# FDTI_USB_Card.net
KiCad netlist of a schematic drawn in Altium Designer
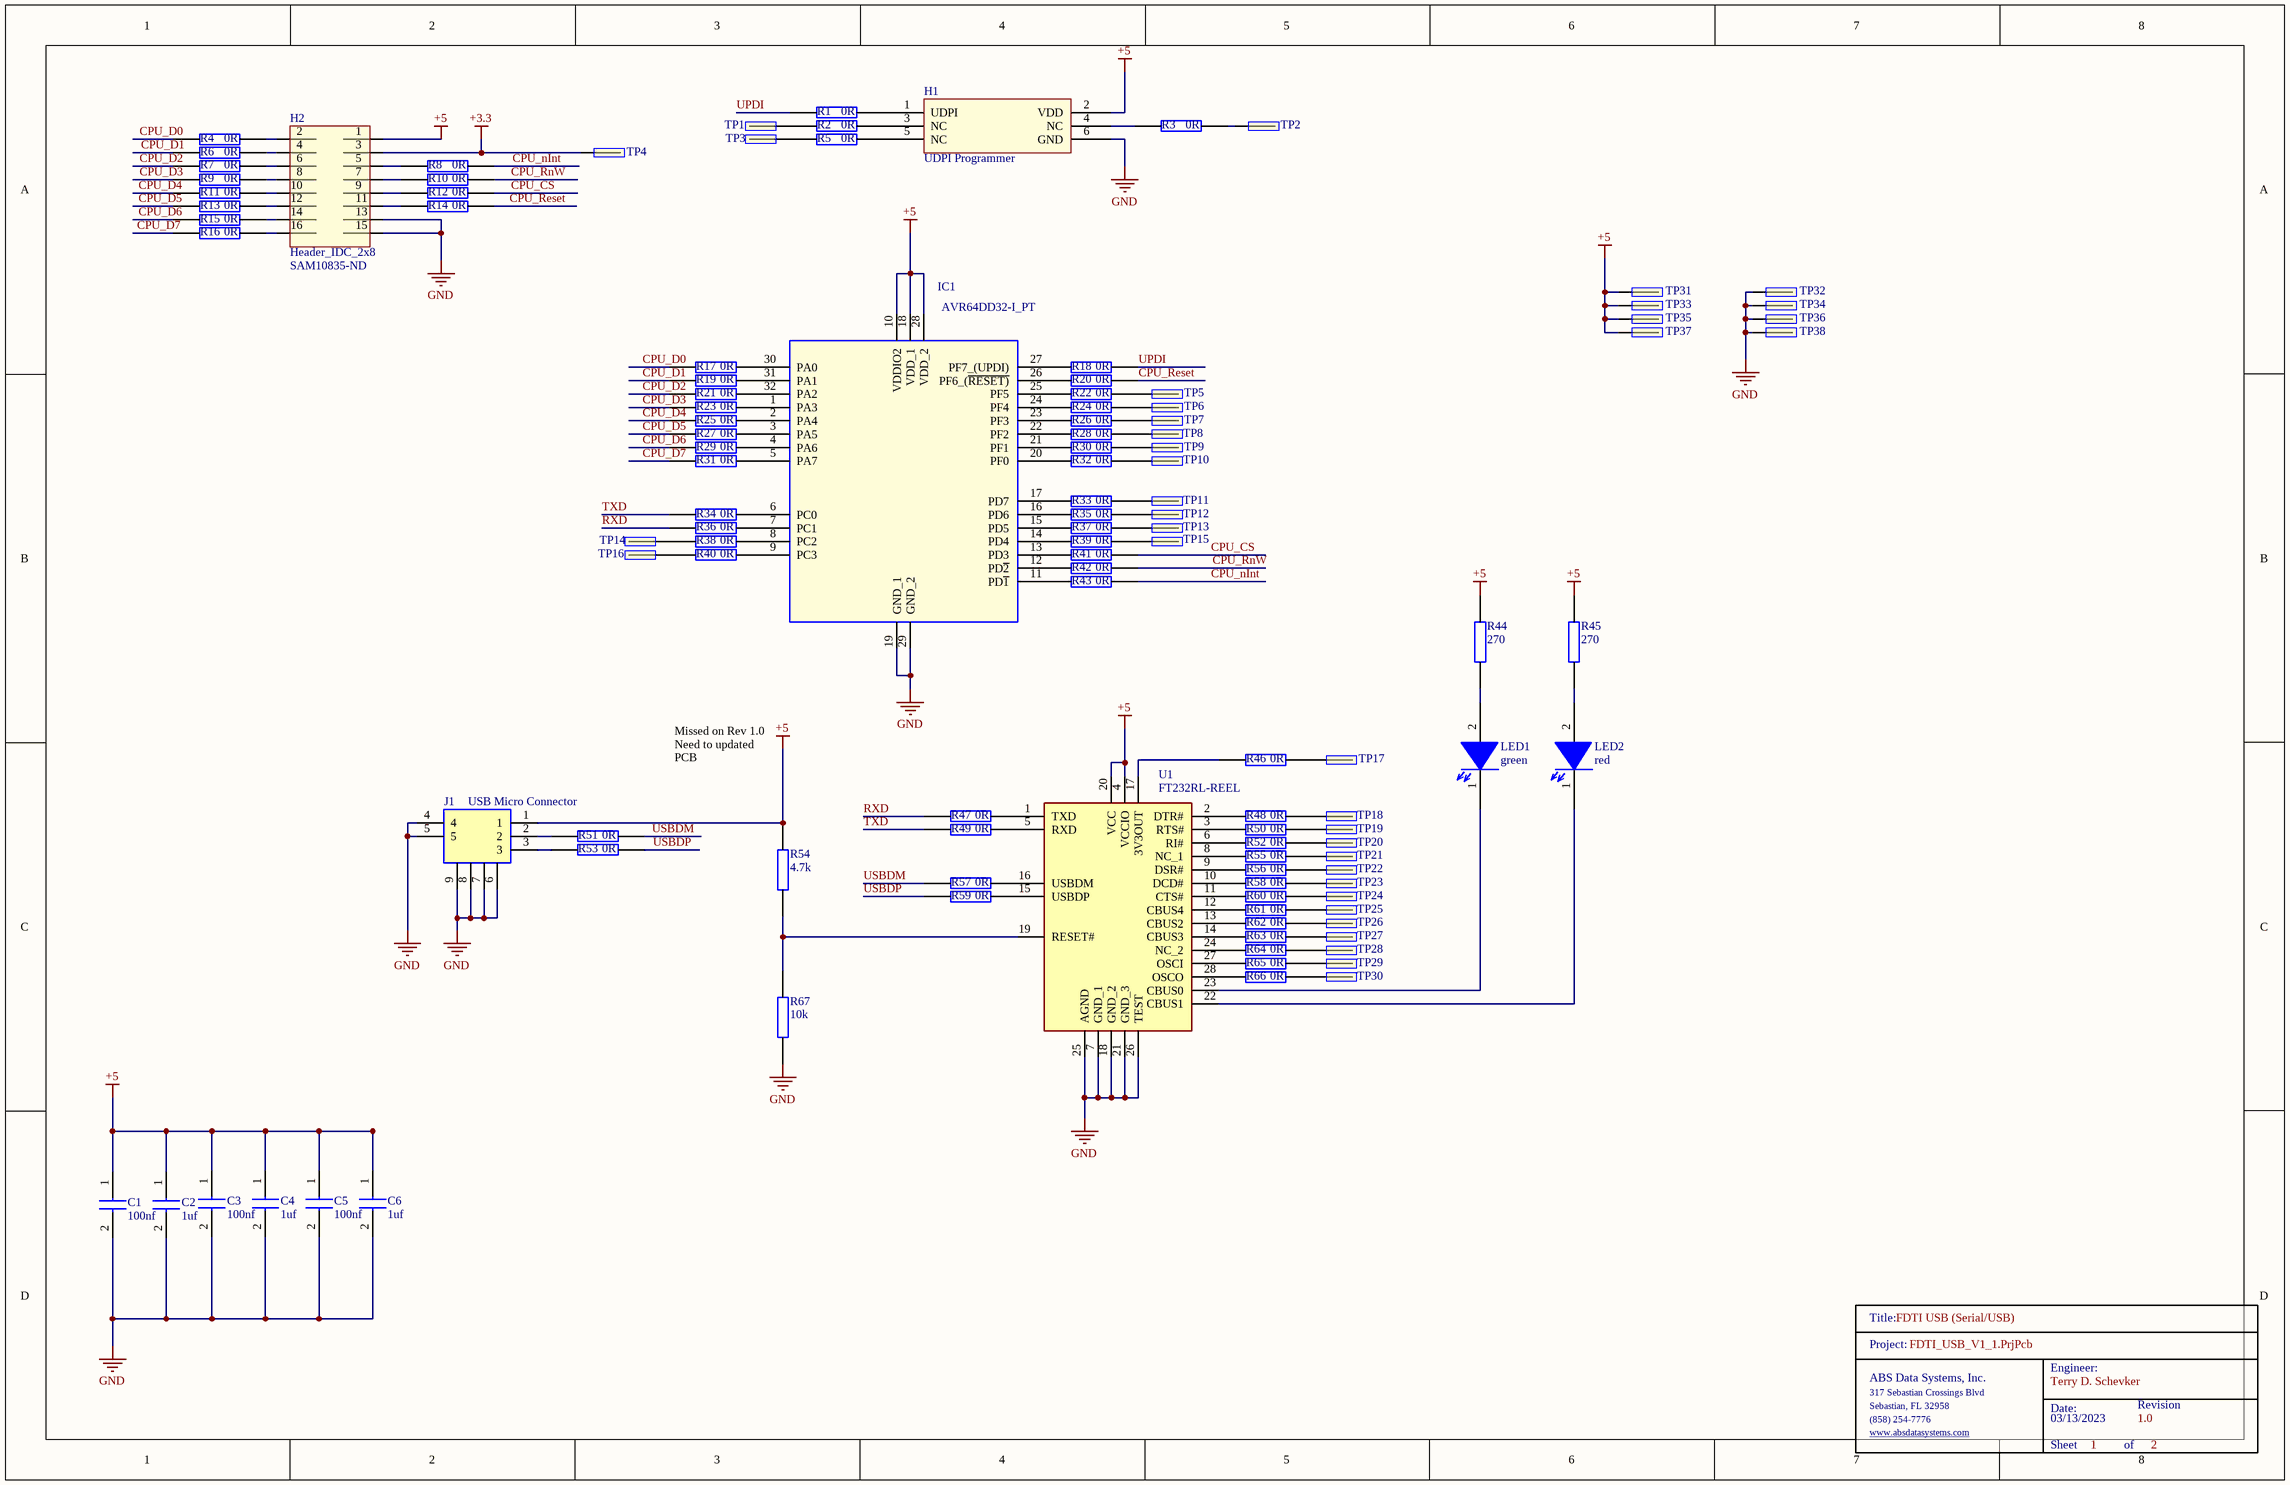
[diagram p0: FDTI_USB_Card.SchDoc]

(export (version "E")
  (design (tool "Eeschema 10.0.6"))
  (components
    (comp (ref "C1")
      (value "100nf")
      (footprint "0603")
      (description "Samsung Electro-Mechanics 0603 100nf")
      (libsource (lib "Capacitors") (part "CL10B104JB8NNNC"))
    )
    (comp (ref "C2")
      (value "1uf")
      (footprint "0603")
      (description "Samsung Electro-Mechanics 0603 1uf")
      (libsource (lib "Capacitors") (part "CL10B105KA8NNNL"))
    )
    (comp (ref "C3")
      (value "100nf")
      (footprint "0603")
      (description "Samsung Electro-Mechanics 0603 100nf")
      (libsource (lib "Capacitors") (part "CL10B104JB8NNNC"))
    )
    (comp (ref "C4")
      (value "1uf")
      (footprint "0603")
      (description "Samsung Electro-Mechanics 0603 1uf")
      (libsource (lib "Capacitors") (part "CL10B105KA8NNNL"))
    )
    (comp (ref "C5")
      (value "100nf")
      (footprint "0603")
      (description "Samsung Electro-Mechanics 0603 100nf")
      (libsource (lib "Capacitors") (part "CL10B104JB8NNNC"))
    )
    (comp (ref "C6")
      (value "1uf")
      (footprint "0603")
      (description "Samsung Electro-Mechanics 0603 1uf")
      (libsource (lib "Capacitors") (part "CL10B105KA8NNNL"))
    )
    (comp (ref "H1")
      (value "UDPI Programmer")
      (footprint "HDR2X3")
      (description "6 Pin 2X3 Through Hole Header")
      (libsource (lib "Misc") (part "UDPI Programmer"))
    )
    (comp (ref "H2")
      (value "Header_IDC_2x8")
      (footprint "HEADER16")
      (description "16 Pin 2x8 Through Hold IDC Connector")
      (fields
        (field (name "MANUFACTURER") "Samtec")
        (field (name "MANUFACTURER PART NUMBER") "TST-108-01-G-D")
        (field (name "SUPPLIER PART NUMBER 1") "SAM10835-ND")
      )
      (libsource (lib "Misc") (part "Header_IDC_2x8"))
    )
    (comp (ref "IC1")
      (value "AVR64DD32-I_PT")
      (footprint "QFP80P900X900X120-32N")
      (description "Integrated Circuit")
      (fields (field (name "MANUFACTURER_PART_NUMBER") "AVR64DD32-I/PT ¦ MULTI-VOLTAGE I/O"))
      (libsource (lib "CPU_Memory") (part "AVR64DD32-I_PT"))
    )
    (comp (ref "J1")
      (value "USB Micro Connector")
      (footprint "Connectors:1734035-2USB")
      (description "USB Micro Connector SMD")
      (fields
        (field (name "MOUSER2 PART NUMBER") "571-1734035-4")
        (field (name "MANUFACTURER_PART_NUMBER") "1734035-4")
      )
      (libsource (lib "Connectors") (part "1734035-4"))
    )
    (comp (ref "LED1")
      (value "green")
      (footprint "0603_Diode")
      (description "Wurth Elektronik 0603 green")
      (fields
        (field (name "MANUFACTURER") "Wurth Electronics")
        (field (name "MANUFACTURER PART NUMBER") "150060GS75000")
      )
      (libsource (lib "Misc") (part "150060GS75000"))
    )
    (comp (ref "LED2")
      (value "red")
      (footprint "0603_Diode")
      (description "Wurth Elektronik 0603 red")
      (fields
        (field (name "MANUFACTURER") "Wurth Electronics")
        (field (name "MANUFACTURER PART NUMBER") "150060GS75000")
      )
      (libsource (lib "Misc") (part "150060RS75000"))
    )
    (comp (ref "R1")
      (value "0R")
      (footprint "0603")
      (description "YAGEO 0603 0 ohm")
      (fields
        (field (name "MOUSER PART NUMBER") "603-RC0603JR-070RL")
        (field (name "MANUFACTURER_PART_NUMBER") "RC0603JR-070RL")
      )
      (libsource (lib "Resistors") (part "RC0603JR-070RL"))
    )
    (comp (ref "R2")
      (value "0R")
      (footprint "0603")
      (description "YAGEO 0603 0 ohm")
      (fields
        (field (name "MOUSER PART NUMBER") "603-RC0603JR-070RL")
        (field (name "MANUFACTURER_PART_NUMBER") "RC0603JR-070RL")
      )
      (libsource (lib "Resistors") (part "RC0603JR-070RL"))
    )
    (comp (ref "R3")
      (value "0R")
      (footprint "0603")
      (description "YAGEO 0603 0 ohm")
      (fields
        (field (name "MOUSER PART NUMBER") "603-RC0603JR-070RL")
        (field (name "MANUFACTURER_PART_NUMBER") "RC0603JR-070RL")
      )
      (libsource (lib "Resistors") (part "RC0603JR-070RL"))
    )
    (comp (ref "R4")
      (value "0R")
      (footprint "0603")
      (description "YAGEO 0603 0 ohm")
      (fields
        (field (name "MOUSER PART NUMBER") "603-RC0603JR-070RL")
        (field (name "MANUFACTURER_PART_NUMBER") "RC0603JR-070RL")
      )
      (libsource (lib "Resistors") (part "RC0603JR-070RL"))
    )
    (comp (ref "R5")
      (value "0R")
      (footprint "0603")
      (description "YAGEO 0603 0 ohm")
      (fields
        (field (name "MOUSER PART NUMBER") "603-RC0603JR-070RL")
        (field (name "MANUFACTURER_PART_NUMBER") "RC0603JR-070RL")
      )
      (libsource (lib "Resistors") (part "RC0603JR-070RL"))
    )
    (comp (ref "R6")
      (value "0R")
      (footprint "0603")
      (description "YAGEO 0603 0 ohm")
      (fields
        (field (name "MOUSER PART NUMBER") "603-RC0603JR-070RL")
        (field (name "MANUFACTURER_PART_NUMBER") "RC0603JR-070RL")
      )
      (libsource (lib "Resistors") (part "RC0603JR-070RL"))
    )
    (comp (ref "R7")
      (value "0R")
      (footprint "0603")
      (description "YAGEO 0603 0 ohm")
      (fields
        (field (name "MOUSER PART NUMBER") "603-RC0603JR-070RL")
        (field (name "MANUFACTURER_PART_NUMBER") "RC0603JR-070RL")
      )
      (libsource (lib "Resistors") (part "RC0603JR-070RL"))
    )
    (comp (ref "R8")
      (value "0R")
      (footprint "0603")
      (description "YAGEO 0603 0 ohm")
      (fields
        (field (name "MOUSER PART NUMBER") "603-RC0603JR-070RL")
        (field (name "MANUFACTURER_PART_NUMBER") "RC0603JR-070RL")
      )
      (libsource (lib "Resistors") (part "RC0603JR-070RL"))
    )
    (comp (ref "R9")
      (value "0R")
      (footprint "0603")
      (description "YAGEO 0603 0 ohm")
      (fields
        (field (name "MOUSER PART NUMBER") "603-RC0603JR-070RL")
        (field (name "MANUFACTURER_PART_NUMBER") "RC0603JR-070RL")
      )
      (libsource (lib "Resistors") (part "RC0603JR-070RL"))
    )
    (comp (ref "R10")
      (value "0R")
      (footprint "0603")
      (description "YAGEO 0603 0 ohm")
      (fields
        (field (name "MOUSER PART NUMBER") "603-RC0603JR-070RL")
        (field (name "MANUFACTURER_PART_NUMBER") "RC0603JR-070RL")
      )
      (libsource (lib "Resistors") (part "RC0603JR-070RL"))
    )
    (comp (ref "R11")
      (value "0R")
      (footprint "0603")
      (description "YAGEO 0603 0 ohm")
      (fields
        (field (name "MOUSER PART NUMBER") "603-RC0603JR-070RL")
        (field (name "MANUFACTURER_PART_NUMBER") "RC0603JR-070RL")
      )
      (libsource (lib "Resistors") (part "RC0603JR-070RL"))
    )
    (comp (ref "R12")
      (value "0R")
      (footprint "0603")
      (description "YAGEO 0603 0 ohm")
      (fields
        (field (name "MOUSER PART NUMBER") "603-RC0603JR-070RL")
        (field (name "MANUFACTURER_PART_NUMBER") "RC0603JR-070RL")
      )
      (libsource (lib "Resistors") (part "RC0603JR-070RL"))
    )
    (comp (ref "R13")
      (value "0R")
      (footprint "0603")
      (description "YAGEO 0603 0 ohm")
      (fields
        (field (name "MOUSER PART NUMBER") "603-RC0603JR-070RL")
        (field (name "MANUFACTURER_PART_NUMBER") "RC0603JR-070RL")
      )
      (libsource (lib "Resistors") (part "RC0603JR-070RL"))
    )
    (comp (ref "R14")
      (value "0R")
      (footprint "0603")
      (description "YAGEO 0603 0 ohm")
      (fields
        (field (name "MOUSER PART NUMBER") "603-RC0603JR-070RL")
        (field (name "MANUFACTURER_PART_NUMBER") "RC0603JR-070RL")
      )
      (libsource (lib "Resistors") (part "RC0603JR-070RL"))
    )
    (comp (ref "R15")
      (value "0R")
      (footprint "0603")
      (description "YAGEO 0603 0 ohm")
      (fields
        (field (name "MOUSER PART NUMBER") "603-RC0603JR-070RL")
        (field (name "MANUFACTURER_PART_NUMBER") "RC0603JR-070RL")
      )
      (libsource (lib "Resistors") (part "RC0603JR-070RL"))
    )
    (comp (ref "R16")
      (value "0R")
      (footprint "0603")
      (description "YAGEO 0603 0 ohm")
      (fields
        (field (name "MOUSER PART NUMBER") "603-RC0603JR-070RL")
        (field (name "MANUFACTURER_PART_NUMBER") "RC0603JR-070RL")
      )
      (libsource (lib "Resistors") (part "RC0603JR-070RL"))
    )
    (comp (ref "R17")
      (value "0R")
      (footprint "0603")
      (description "YAGEO 0603 0 ohm")
      (fields
        (field (name "MOUSER PART NUMBER") "603-RC0603JR-070RL")
        (field (name "MANUFACTURER_PART_NUMBER") "RC0603JR-070RL")
      )
      (libsource (lib "Resistors") (part "RC0603JR-070RL"))
    )
    (comp (ref "R18")
      (value "0R")
      (footprint "0603")
      (description "YAGEO 0603 0 ohm")
      (fields
        (field (name "MOUSER PART NUMBER") "603-RC0603JR-070RL")
        (field (name "MANUFACTURER_PART_NUMBER") "RC0603JR-070RL")
      )
      (libsource (lib "Resistors") (part "RC0603JR-070RL"))
    )
    (comp (ref "R19")
      (value "0R")
      (footprint "0603")
      (description "YAGEO 0603 0 ohm")
      (fields
        (field (name "MOUSER PART NUMBER") "603-RC0603JR-070RL")
        (field (name "MANUFACTURER_PART_NUMBER") "RC0603JR-070RL")
      )
      (libsource (lib "Resistors") (part "RC0603JR-070RL"))
    )
    (comp (ref "R20")
      (value "0R")
      (footprint "0603")
      (description "YAGEO 0603 0 ohm")
      (fields
        (field (name "MOUSER PART NUMBER") "603-RC0603JR-070RL")
        (field (name "MANUFACTURER_PART_NUMBER") "RC0603JR-070RL")
      )
      (libsource (lib "Resistors") (part "RC0603JR-070RL"))
    )
    (comp (ref "R21")
      (value "0R")
      (footprint "0603")
      (description "YAGEO 0603 0 ohm")
      (fields
        (field (name "MOUSER PART NUMBER") "603-RC0603JR-070RL")
        (field (name "MANUFACTURER_PART_NUMBER") "RC0603JR-070RL")
      )
      (libsource (lib "Resistors") (part "RC0603JR-070RL"))
    )
    (comp (ref "R22")
      (value "0R")
      (footprint "0603")
      (description "YAGEO 0603 0 ohm")
      (fields
        (field (name "MOUSER PART NUMBER") "603-RC0603JR-070RL")
        (field (name "MANUFACTURER_PART_NUMBER") "RC0603JR-070RL")
      )
      (libsource (lib "Resistors") (part "RC0603JR-070RL"))
    )
    (comp (ref "R23")
      (value "0R")
      (footprint "0603")
      (description "YAGEO 0603 0 ohm")
      (fields
        (field (name "MOUSER PART NUMBER") "603-RC0603JR-070RL")
        (field (name "MANUFACTURER_PART_NUMBER") "RC0603JR-070RL")
      )
      (libsource (lib "Resistors") (part "RC0603JR-070RL"))
    )
    (comp (ref "R24")
      (value "0R")
      (footprint "0603")
      (description "YAGEO 0603 0 ohm")
      (fields
        (field (name "MOUSER PART NUMBER") "603-RC0603JR-070RL")
        (field (name "MANUFACTURER_PART_NUMBER") "RC0603JR-070RL")
      )
      (libsource (lib "Resistors") (part "RC0603JR-070RL"))
    )
    (comp (ref "R25")
      (value "0R")
      (footprint "0603")
      (description "YAGEO 0603 0 ohm")
      (fields
        (field (name "MOUSER PART NUMBER") "603-RC0603JR-070RL")
        (field (name "MANUFACTURER_PART_NUMBER") "RC0603JR-070RL")
      )
      (libsource (lib "Resistors") (part "RC0603JR-070RL"))
    )
    (comp (ref "R26")
      (value "0R")
      (footprint "0603")
      (description "YAGEO 0603 0 ohm")
      (fields
        (field (name "MOUSER PART NUMBER") "603-RC0603JR-070RL")
        (field (name "MANUFACTURER_PART_NUMBER") "RC0603JR-070RL")
      )
      (libsource (lib "Resistors") (part "RC0603JR-070RL"))
    )
    (comp (ref "R27")
      (value "0R")
      (footprint "0603")
      (description "YAGEO 0603 0 ohm")
      (fields
        (field (name "MOUSER PART NUMBER") "603-RC0603JR-070RL")
        (field (name "MANUFACTURER_PART_NUMBER") "RC0603JR-070RL")
      )
      (libsource (lib "Resistors") (part "RC0603JR-070RL"))
    )
    (comp (ref "R28")
      (value "0R")
      (footprint "0603")
      (description "YAGEO 0603 0 ohm")
      (fields
        (field (name "MOUSER PART NUMBER") "603-RC0603JR-070RL")
        (field (name "MANUFACTURER_PART_NUMBER") "RC0603JR-070RL")
      )
      (libsource (lib "Resistors") (part "RC0603JR-070RL"))
    )
    (comp (ref "R29")
      (value "0R")
      (footprint "0603")
      (description "YAGEO 0603 0 ohm")
      (fields
        (field (name "MOUSER PART NUMBER") "603-RC0603JR-070RL")
        (field (name "MANUFACTURER_PART_NUMBER") "RC0603JR-070RL")
      )
      (libsource (lib "Resistors") (part "RC0603JR-070RL"))
    )
    (comp (ref "R30")
      (value "0R")
      (footprint "0603")
      (description "YAGEO 0603 0 ohm")
      (fields
        (field (name "MOUSER PART NUMBER") "603-RC0603JR-070RL")
        (field (name "MANUFACTURER_PART_NUMBER") "RC0603JR-070RL")
      )
      (libsource (lib "Resistors") (part "RC0603JR-070RL"))
    )
    (comp (ref "R31")
      (value "0R")
      (footprint "0603")
      (description "YAGEO 0603 0 ohm")
      (fields
        (field (name "MOUSER PART NUMBER") "603-RC0603JR-070RL")
        (field (name "MANUFACTURER_PART_NUMBER") "RC0603JR-070RL")
      )
      (libsource (lib "Resistors") (part "RC0603JR-070RL"))
    )
    (comp (ref "R32")
      (value "0R")
      (footprint "0603")
      (description "YAGEO 0603 0 ohm")
      (fields
        (field (name "MOUSER PART NUMBER") "603-RC0603JR-070RL")
        (field (name "MANUFACTURER_PART_NUMBER") "RC0603JR-070RL")
      )
      (libsource (lib "Resistors") (part "RC0603JR-070RL"))
    )
    (comp (ref "R33")
      (value "0R")
      (footprint "0603")
      (description "YAGEO 0603 0 ohm")
      (fields
        (field (name "MOUSER PART NUMBER") "603-RC0603JR-070RL")
        (field (name "MANUFACTURER_PART_NUMBER") "RC0603JR-070RL")
      )
      (libsource (lib "Resistors") (part "RC0603JR-070RL"))
    )
    (comp (ref "R34")
      (value "0R")
      (footprint "0603")
      (description "YAGEO 0603 0 ohm")
      (fields
        (field (name "MOUSER PART NUMBER") "603-RC0603JR-070RL")
        (field (name "MANUFACTURER_PART_NUMBER") "RC0603JR-070RL")
      )
      (libsource (lib "Resistors") (part "RC0603JR-070RL"))
    )
    (comp (ref "R35")
      (value "0R")
      (footprint "0603")
      (description "YAGEO 0603 0 ohm")
      (fields
        (field (name "MOUSER PART NUMBER") "603-RC0603JR-070RL")
        (field (name "MANUFACTURER_PART_NUMBER") "RC0603JR-070RL")
      )
      (libsource (lib "Resistors") (part "RC0603JR-070RL"))
    )
    (comp (ref "R36")
      (value "0R")
      (footprint "0603")
      (description "YAGEO 0603 0 ohm")
      (fields
        (field (name "MOUSER PART NUMBER") "603-RC0603JR-070RL")
        (field (name "MANUFACTURER_PART_NUMBER") "RC0603JR-070RL")
      )
      (libsource (lib "Resistors") (part "RC0603JR-070RL"))
    )
    (comp (ref "R37")
      (value "0R")
      (footprint "0603")
      (description "YAGEO 0603 0 ohm")
      (fields
        (field (name "MOUSER PART NUMBER") "603-RC0603JR-070RL")
        (field (name "MANUFACTURER_PART_NUMBER") "RC0603JR-070RL")
      )
      (libsource (lib "Resistors") (part "RC0603JR-070RL"))
    )
    (comp (ref "R38")
      (value "0R")
      (footprint "0603")
      (description "YAGEO 0603 0 ohm")
      (fields
        (field (name "MOUSER PART NUMBER") "603-RC0603JR-070RL")
        (field (name "MANUFACTURER_PART_NUMBER") "RC0603JR-070RL")
      )
      (libsource (lib "Resistors") (part "RC0603JR-070RL"))
    )
    (comp (ref "R39")
      (value "0R")
      (footprint "0603")
      (description "YAGEO 0603 0 ohm")
      (fields
        (field (name "MOUSER PART NUMBER") "603-RC0603JR-070RL")
        (field (name "MANUFACTURER_PART_NUMBER") "RC0603JR-070RL")
      )
      (libsource (lib "Resistors") (part "RC0603JR-070RL"))
    )
    (comp (ref "R40")
      (value "0R")
      (footprint "0603")
      (description "YAGEO 0603 0 ohm")
      (fields
        (field (name "MOUSER PART NUMBER") "603-RC0603JR-070RL")
        (field (name "MANUFACTURER_PART_NUMBER") "RC0603JR-070RL")
      )
      (libsource (lib "Resistors") (part "RC0603JR-070RL"))
    )
    (comp (ref "R41")
      (value "0R")
      (footprint "0603")
      (description "YAGEO 0603 0 ohm")
      (fields
        (field (name "MOUSER PART NUMBER") "603-RC0603JR-070RL")
        (field (name "MANUFACTURER_PART_NUMBER") "RC0603JR-070RL")
      )
      (libsource (lib "Resistors") (part "RC0603JR-070RL"))
    )
    (comp (ref "R42")
      (value "0R")
      (footprint "0603")
      (description "YAGEO 0603 0 ohm")
      (fields
        (field (name "MOUSER PART NUMBER") "603-RC0603JR-070RL")
        (field (name "MANUFACTURER_PART_NUMBER") "RC0603JR-070RL")
      )
      (libsource (lib "Resistors") (part "RC0603JR-070RL"))
    )
    (comp (ref "R43")
      (value "0R")
      (footprint "0603")
      (description "YAGEO 0603 0 ohm")
      (fields
        (field (name "MOUSER PART NUMBER") "603-RC0603JR-070RL")
        (field (name "MANUFACTURER_PART_NUMBER") "RC0603JR-070RL")
      )
      (libsource (lib "Resistors") (part "RC0603JR-070RL"))
    )
    (comp (ref "R44")
      (value "270")
      (footprint "0603")
      (description "YAGEO 0603 270 ohm")
      (fields
        (field (name "MOUSER PART NUMBER") "603-RC0603JR-070RL")
        (field (name "MANUFACTURER_PART_NUMBER") "RC0603JR-070RL")
      )
      (libsource (lib "Resistors") (part "RC0603JR-07270RL"))
    )
    (comp (ref "R45")
      (value "270")
      (footprint "0603")
      (description "YAGEO 0603 270 ohm")
      (fields
        (field (name "MOUSER PART NUMBER") "603-RC0603JR-070RL")
        (field (name "MANUFACTURER_PART_NUMBER") "RC0603JR-070RL")
      )
      (libsource (lib "Resistors") (part "RC0603JR-07270RL"))
    )
    (comp (ref "R46")
      (value "0R")
      (footprint "0603")
      (description "YAGEO 0603 0 ohm")
      (fields
        (field (name "MOUSER PART NUMBER") "603-RC0603JR-070RL")
        (field (name "MANUFACTURER_PART_NUMBER") "RC0603JR-070RL")
      )
      (libsource (lib "Resistors") (part "RC0603JR-070RL"))
    )
    (comp (ref "R47")
      (value "0R")
      (footprint "0603")
      (description "YAGEO 0603 0 ohm")
      (fields
        (field (name "MOUSER PART NUMBER") "603-RC0603JR-070RL")
        (field (name "MANUFACTURER_PART_NUMBER") "RC0603JR-070RL")
      )
      (libsource (lib "Resistors") (part "RC0603JR-070RL"))
    )
    (comp (ref "R48")
      (value "0R")
      (footprint "0603")
      (description "YAGEO 0603 0 ohm")
      (fields
        (field (name "MOUSER PART NUMBER") "603-RC0603JR-070RL")
        (field (name "MANUFACTURER_PART_NUMBER") "RC0603JR-070RL")
      )
      (libsource (lib "Resistors") (part "RC0603JR-070RL"))
    )
    (comp (ref "R49")
      (value "0R")
      (footprint "0603")
      (description "YAGEO 0603 0 ohm")
      (fields
        (field (name "MOUSER PART NUMBER") "603-RC0603JR-070RL")
        (field (name "MANUFACTURER_PART_NUMBER") "RC0603JR-070RL")
      )
      (libsource (lib "Resistors") (part "RC0603JR-070RL"))
    )
    (comp (ref "R50")
      (value "0R")
      (footprint "0603")
      (description "YAGEO 0603 0 ohm")
      (fields
        (field (name "MOUSER PART NUMBER") "603-RC0603JR-070RL")
        (field (name "MANUFACTURER_PART_NUMBER") "RC0603JR-070RL")
      )
      (libsource (lib "Resistors") (part "RC0603JR-070RL"))
    )
    (comp (ref "R51")
      (value "0R")
      (footprint "0603")
      (description "YAGEO 0603 0 ohm")
      (fields
        (field (name "MOUSER PART NUMBER") "603-RC0603JR-070RL")
        (field (name "MANUFACTURER_PART_NUMBER") "RC0603JR-070RL")
      )
      (libsource (lib "Resistors") (part "RC0603JR-070RL"))
    )
    (comp (ref "R52")
      (value "0R")
      (footprint "0603")
      (description "YAGEO 0603 0 ohm")
      (fields
        (field (name "MOUSER PART NUMBER") "603-RC0603JR-070RL")
        (field (name "MANUFACTURER_PART_NUMBER") "RC0603JR-070RL")
      )
      (libsource (lib "Resistors") (part "RC0603JR-070RL"))
    )
    (comp (ref "R53")
      (value "0R")
      (footprint "0603")
      (description "YAGEO 0603 0 ohm")
      (fields
        (field (name "MOUSER PART NUMBER") "603-RC0603JR-070RL")
        (field (name "MANUFACTURER_PART_NUMBER") "RC0603JR-070RL")
      )
      (libsource (lib "Resistors") (part "RC0603JR-070RL"))
    )
    (comp (ref "R54")
      (value "4.7k")
      (footprint "0603")
      (description "YAGEO 0603 4.7k")
      (fields
        (field (name "MOUSER PART NUMBER") "603-RC0603JR-070RL")
        (field (name "MANUFACTURER_PART_NUMBER") "RC0603JR-070RL")
      )
      (libsource (lib "Resistors") (part "RC0603FR-104K7L"))
    )
    (comp (ref "R55")
      (value "0R")
      (footprint "0603")
      (description "YAGEO 0603 0 ohm")
      (fields
        (field (name "MOUSER PART NUMBER") "603-RC0603JR-070RL")
        (field (name "MANUFACTURER_PART_NUMBER") "RC0603JR-070RL")
      )
      (libsource (lib "Resistors") (part "RC0603JR-070RL"))
    )
    (comp (ref "R56")
      (value "0R")
      (footprint "0603")
      (description "YAGEO 0603 0 ohm")
      (fields
        (field (name "MOUSER PART NUMBER") "603-RC0603JR-070RL")
        (field (name "MANUFACTURER_PART_NUMBER") "RC0603JR-070RL")
      )
      (libsource (lib "Resistors") (part "RC0603JR-070RL"))
    )
    (comp (ref "R57")
      (value "0R")
      (footprint "0603")
      (description "YAGEO 0603 0 ohm")
      (fields
        (field (name "MOUSER PART NUMBER") "603-RC0603JR-070RL")
        (field (name "MANUFACTURER_PART_NUMBER") "RC0603JR-070RL")
      )
      (libsource (lib "Resistors") (part "RC0603JR-070RL"))
    )
    (comp (ref "R58")
      (value "0R")
      (footprint "0603")
      (description "YAGEO 0603 0 ohm")
      (fields
        (field (name "MOUSER PART NUMBER") "603-RC0603JR-070RL")
        (field (name "MANUFACTURER_PART_NUMBER") "RC0603JR-070RL")
      )
      (libsource (lib "Resistors") (part "RC0603JR-070RL"))
    )
    (comp (ref "R59")
      (value "0R")
      (footprint "0603")
      (description "YAGEO 0603 0 ohm")
      (fields
        (field (name "MOUSER PART NUMBER") "603-RC0603JR-070RL")
        (field (name "MANUFACTURER_PART_NUMBER") "RC0603JR-070RL")
      )
      (libsource (lib "Resistors") (part "RC0603JR-070RL"))
    )
    (comp (ref "R60")
      (value "0R")
      (footprint "0603")
      (description "YAGEO 0603 0 ohm")
      (fields
        (field (name "MOUSER PART NUMBER") "603-RC0603JR-070RL")
        (field (name "MANUFACTURER_PART_NUMBER") "RC0603JR-070RL")
      )
      (libsource (lib "Resistors") (part "RC0603JR-070RL"))
    )
    (comp (ref "R61")
      (value "0R")
      (footprint "0603")
      (description "YAGEO 0603 0 ohm")
      (fields
        (field (name "MOUSER PART NUMBER") "603-RC0603JR-070RL")
        (field (name "MANUFACTURER_PART_NUMBER") "RC0603JR-070RL")
      )
      (libsource (lib "Resistors") (part "RC0603JR-070RL"))
    )
    (comp (ref "R62")
      (value "0R")
      (footprint "0603")
      (description "YAGEO 0603 0 ohm")
      (fields
        (field (name "MOUSER PART NUMBER") "603-RC0603JR-070RL")
        (field (name "MANUFACTURER_PART_NUMBER") "RC0603JR-070RL")
      )
      (libsource (lib "Resistors") (part "RC0603JR-070RL"))
    )
    (comp (ref "R63")
      (value "0R")
      (footprint "0603")
      (description "YAGEO 0603 0 ohm")
      (fields
        (field (name "MOUSER PART NUMBER") "603-RC0603JR-070RL")
        (field (name "MANUFACTURER_PART_NUMBER") "RC0603JR-070RL")
      )
      (libsource (lib "Resistors") (part "RC0603JR-070RL"))
    )
    (comp (ref "R64")
      (value "0R")
      (footprint "0603")
      (description "YAGEO 0603 0 ohm")
      (fields
        (field (name "MOUSER PART NUMBER") "603-RC0603JR-070RL")
        (field (name "MANUFACTURER_PART_NUMBER") "RC0603JR-070RL")
      )
      (libsource (lib "Resistors") (part "RC0603JR-070RL"))
    )
    (comp (ref "R65")
      (value "0R")
      (footprint "0603")
      (description "YAGEO 0603 0 ohm")
      (fields
        (field (name "MOUSER PART NUMBER") "603-RC0603JR-070RL")
        (field (name "MANUFACTURER_PART_NUMBER") "RC0603JR-070RL")
      )
      (libsource (lib "Resistors") (part "RC0603JR-070RL"))
    )
    (comp (ref "R66")
      (value "0R")
      (footprint "0603")
      (description "YAGEO 0603 0 ohm")
      (fields
        (field (name "MOUSER PART NUMBER") "603-RC0603JR-070RL")
        (field (name "MANUFACTURER_PART_NUMBER") "RC0603JR-070RL")
      )
      (libsource (lib "Resistors") (part "RC0603JR-070RL"))
    )
    (comp (ref "R67")
      (value "10k")
      (footprint "0603")
      (description "YAGEO 0603 10k ohm")
      (fields
        (field (name "MOUSER PART NUMBER") "603-RC0603JR-070RL")
        (field (name "MANUFACTURER_PART_NUMBER") "RC0603JR-070RL")
      )
      (libsource (lib "Resistors") (part "RC0603JR-0710KL"))
    )
    (comp (ref "TitleBlock_1") (value "TitleBlock") (libsource (lib "Misc") (part "TitleBlock")))
    (comp (ref "TP1")
      (value "TP")
      (footprint "TP")
      (fields
        (field (name "MANUFACTURER") "Samtec")
        (field (name "MANUFACTURER PART NUMBER") "TST-105-01-G-D")
      )
      (libsource (lib "") (part "TP_2"))
    )
    (comp (ref "TP2")
      (value "TP")
      (footprint "TP")
      (fields
        (field (name "MANUFACTURER") "Samtec")
        (field (name "MANUFACTURER PART NUMBER") "TST-105-01-G-D")
      )
      (libsource (lib "Misc") (part "TP"))
    )
    (comp (ref "TP3")
      (value "TP")
      (footprint "TP")
      (fields
        (field (name "MANUFACTURER") "Samtec")
        (field (name "MANUFACTURER PART NUMBER") "TST-105-01-G-D")
      )
      (libsource (lib "") (part "TP_2"))
    )
    (comp (ref "TP4")
      (value "TP")
      (footprint "TP")
      (fields
        (field (name "MANUFACTURER") "Samtec")
        (field (name "MANUFACTURER PART NUMBER") "TST-105-01-G-D")
      )
      (libsource (lib "Misc") (part "TP"))
    )
    (comp (ref "TP5")
      (value "TP")
      (footprint "TP")
      (fields
        (field (name "MANUFACTURER") "Samtec")
        (field (name "MANUFACTURER PART NUMBER") "TST-105-01-G-D")
      )
      (libsource (lib "Misc") (part "TP"))
    )
    (comp (ref "TP6")
      (value "TP")
      (footprint "TP")
      (fields
        (field (name "MANUFACTURER") "Samtec")
        (field (name "MANUFACTURER PART NUMBER") "TST-105-01-G-D")
      )
      (libsource (lib "Misc") (part "TP"))
    )
    (comp (ref "TP7")
      (value "TP")
      (footprint "TP")
      (fields
        (field (name "MANUFACTURER") "Samtec")
        (field (name "MANUFACTURER PART NUMBER") "TST-105-01-G-D")
      )
      (libsource (lib "Misc") (part "TP"))
    )
    (comp (ref "TP8")
      (value "TP")
      (footprint "TP")
      (fields
        (field (name "MANUFACTURER") "Samtec")
        (field (name "MANUFACTURER PART NUMBER") "TST-105-01-G-D")
      )
      (libsource (lib "Misc") (part "TP"))
    )
    (comp (ref "TP9")
      (value "TP")
      (footprint "TP")
      (fields
        (field (name "MANUFACTURER") "Samtec")
        (field (name "MANUFACTURER PART NUMBER") "TST-105-01-G-D")
      )
      (libsource (lib "Misc") (part "TP"))
    )
    (comp (ref "TP10")
      (value "TP")
      (footprint "TP")
      (fields
        (field (name "MANUFACTURER") "Samtec")
        (field (name "MANUFACTURER PART NUMBER") "TST-105-01-G-D")
      )
      (libsource (lib "Misc") (part "TP"))
    )
    (comp (ref "TP11")
      (value "TP")
      (footprint "TP")
      (fields
        (field (name "MANUFACTURER") "Samtec")
        (field (name "MANUFACTURER PART NUMBER") "TST-105-01-G-D")
      )
      (libsource (lib "Misc") (part "TP"))
    )
    (comp (ref "TP12")
      (value "TP")
      (footprint "TP")
      (fields
        (field (name "MANUFACTURER") "Samtec")
        (field (name "MANUFACTURER PART NUMBER") "TST-105-01-G-D")
      )
      (libsource (lib "Misc") (part "TP"))
    )
    (comp (ref "TP13")
      (value "TP")
      (footprint "TP")
      (fields
        (field (name "MANUFACTURER") "Samtec")
        (field (name "MANUFACTURER PART NUMBER") "TST-105-01-G-D")
      )
      (libsource (lib "Misc") (part "TP"))
    )
    (comp (ref "TP14")
      (value "TP")
      (footprint "TP")
      (fields
        (field (name "MANUFACTURER") "Samtec")
        (field (name "MANUFACTURER PART NUMBER") "TST-105-01-G-D")
      )
      (libsource (lib "") (part "TP_2"))
    )
    (comp (ref "TP15")
      (value "TP")
      (footprint "TP")
      (fields
        (field (name "MANUFACTURER") "Samtec")
        (field (name "MANUFACTURER PART NUMBER") "TST-105-01-G-D")
      )
      (libsource (lib "Misc") (part "TP"))
    )
    (comp (ref "TP16")
      (value "TP")
      (footprint "TP")
      (fields
        (field (name "MANUFACTURER") "Samtec")
        (field (name "MANUFACTURER PART NUMBER") "TST-105-01-G-D")
      )
      (libsource (lib "") (part "TP_2"))
    )
    (comp (ref "TP17")
      (value "TP")
      (footprint "TP")
      (fields
        (field (name "MANUFACTURER") "Samtec")
        (field (name "MANUFACTURER PART NUMBER") "TST-105-01-G-D")
      )
      (libsource (lib "Misc") (part "TP"))
    )
    (comp (ref "TP18")
      (value "TP")
      (footprint "TP")
      (fields
        (field (name "MANUFACTURER") "Samtec")
        (field (name "MANUFACTURER PART NUMBER") "TST-105-01-G-D")
      )
      (libsource (lib "Misc") (part "TP"))
    )
    (comp (ref "TP19")
      (value "TP")
      (footprint "TP")
      (fields
        (field (name "MANUFACTURER") "Samtec")
        (field (name "MANUFACTURER PART NUMBER") "TST-105-01-G-D")
      )
      (libsource (lib "Misc") (part "TP"))
    )
    (comp (ref "TP20")
      (value "TP")
      (footprint "TP")
      (fields
        (field (name "MANUFACTURER") "Samtec")
        (field (name "MANUFACTURER PART NUMBER") "TST-105-01-G-D")
      )
      (libsource (lib "Misc") (part "TP"))
    )
    (comp (ref "TP21")
      (value "TP")
      (footprint "TP")
      (fields
        (field (name "MANUFACTURER") "Samtec")
        (field (name "MANUFACTURER PART NUMBER") "TST-105-01-G-D")
      )
      (libsource (lib "Misc") (part "TP"))
    )
    (comp (ref "TP22")
      (value "TP")
      (footprint "TP")
      (fields
        (field (name "MANUFACTURER") "Samtec")
        (field (name "MANUFACTURER PART NUMBER") "TST-105-01-G-D")
      )
      (libsource (lib "Misc") (part "TP"))
    )
    (comp (ref "TP23")
      (value "TP")
      (footprint "TP")
      (fields
        (field (name "MANUFACTURER") "Samtec")
        (field (name "MANUFACTURER PART NUMBER") "TST-105-01-G-D")
      )
      (libsource (lib "Misc") (part "TP"))
    )
    (comp (ref "TP24")
      (value "TP")
      (footprint "TP")
      (fields
        (field (name "MANUFACTURER") "Samtec")
        (field (name "MANUFACTURER PART NUMBER") "TST-105-01-G-D")
      )
      (libsource (lib "Misc") (part "TP"))
    )
    (comp (ref "TP25")
      (value "TP")
      (footprint "TP")
      (fields
        (field (name "MANUFACTURER") "Samtec")
        (field (name "MANUFACTURER PART NUMBER") "TST-105-01-G-D")
      )
      (libsource (lib "Misc") (part "TP"))
    )
    (comp (ref "TP26")
      (value "TP")
      (footprint "TP")
      (fields
        (field (name "MANUFACTURER") "Samtec")
        (field (name "MANUFACTURER PART NUMBER") "TST-105-01-G-D")
      )
      (libsource (lib "Misc") (part "TP"))
    )
    (comp (ref "TP27")
      (value "TP")
      (footprint "TP")
      (fields
        (field (name "MANUFACTURER") "Samtec")
        (field (name "MANUFACTURER PART NUMBER") "TST-105-01-G-D")
      )
      (libsource (lib "Misc") (part "TP"))
    )
    (comp (ref "TP28")
      (value "TP")
      (footprint "TP")
      (fields
        (field (name "MANUFACTURER") "Samtec")
        (field (name "MANUFACTURER PART NUMBER") "TST-105-01-G-D")
      )
      (libsource (lib "Misc") (part "TP"))
    )
    (comp (ref "TP29")
      (value "TP")
      (footprint "TP")
      (fields
        (field (name "MANUFACTURER") "Samtec")
        (field (name "MANUFACTURER PART NUMBER") "TST-105-01-G-D")
      )
      (libsource (lib "Misc") (part "TP"))
    )
    (comp (ref "TP30")
      (value "TP")
      (footprint "TP")
      (fields
        (field (name "MANUFACTURER") "Samtec")
        (field (name "MANUFACTURER PART NUMBER") "TST-105-01-G-D")
      )
      (libsource (lib "Misc") (part "TP"))
    )
    (comp (ref "TP31")
      (value "TP")
      (footprint "TP")
      (fields
        (field (name "MANUFACTURER") "Samtec")
        (field (name "MANUFACTURER PART NUMBER") "TST-105-01-G-D")
      )
      (libsource (lib "") (part "TP_1"))
    )
    (comp (ref "TP32")
      (value "TP")
      (footprint "TP")
      (fields
        (field (name "MANUFACTURER") "Samtec")
        (field (name "MANUFACTURER PART NUMBER") "TST-105-01-G-D")
      )
      (libsource (lib "") (part "TP_1"))
    )
    (comp (ref "TP33")
      (value "TP")
      (footprint "TP")
      (fields
        (field (name "MANUFACTURER") "Samtec")
        (field (name "MANUFACTURER PART NUMBER") "TST-105-01-G-D")
      )
      (libsource (lib "") (part "TP_1"))
    )
    (comp (ref "TP34")
      (value "TP")
      (footprint "TP")
      (fields
        (field (name "MANUFACTURER") "Samtec")
        (field (name "MANUFACTURER PART NUMBER") "TST-105-01-G-D")
      )
      (libsource (lib "") (part "TP_1"))
    )
    (comp (ref "TP35")
      (value "TP")
      (footprint "TP")
      (fields
        (field (name "MANUFACTURER") "Samtec")
        (field (name "MANUFACTURER PART NUMBER") "TST-105-01-G-D")
      )
      (libsource (lib "") (part "TP_1"))
    )
    (comp (ref "TP36")
      (value "TP")
      (footprint "TP")
      (fields
        (field (name "MANUFACTURER") "Samtec")
        (field (name "MANUFACTURER PART NUMBER") "TST-105-01-G-D")
      )
      (libsource (lib "") (part "TP_1"))
    )
    (comp (ref "TP37")
      (value "TP")
      (footprint "TP")
      (fields
        (field (name "MANUFACTURER") "Samtec")
        (field (name "MANUFACTURER PART NUMBER") "TST-105-01-G-D")
      )
      (libsource (lib "") (part "TP_1"))
    )
    (comp (ref "TP38")
      (value "TP")
      (footprint "TP")
      (fields
        (field (name "MANUFACTURER") "Samtec")
        (field (name "MANUFACTURER PART NUMBER") "TST-105-01-G-D")
      )
      (libsource (lib "") (part "TP_1"))
    )
    (comp (ref "U1")
      (value "FT232RL-REEL")
      (footprint "Misc:SOIC-28_Narrow")
      (description "USB-Serial SMD")
      (libsource (lib "Misc") (part "FT232RL-REEL"))
    )
  )
  (nets
    (net (code "1") (name "+3.3") (class "Default")
      (node (ref "H2") (pin "3") (pinfunction "3_3") (pintype "passive"))
      (node (ref "TP4") (pin "1") (pinfunction "1_1") (pintype "passive"))
    )
    (net (code "2") (name "+5") (class "Default")
      (node (ref "C1") (pin "1") (pinfunction "1_1") (pintype "passive"))
      (node (ref "C2") (pin "1") (pinfunction "1_1") (pintype "passive"))
      (node (ref "C3") (pin "1") (pinfunction "1_1") (pintype "passive"))
      (node (ref "C4") (pin "1") (pinfunction "1_1") (pintype "passive"))
      (node (ref "C5") (pin "1") (pinfunction "1_1") (pintype "passive"))
      (node (ref "C6") (pin "1") (pinfunction "1_1") (pintype "passive"))
      (node (ref "H1") (pin "2") (pinfunction "VDD_2") (pintype "passive"))
      (node (ref "H2") (pin "1") (pinfunction "1_1") (pintype "passive"))
      (node (ref "IC1") (pin "10") (pinfunction "VDDIO2_10") (pintype "passive"))
      (node (ref "IC1") (pin "18") (pinfunction "VDD_1_18") (pintype "passive"))
      (node (ref "IC1") (pin "28") (pinfunction "VDD_2_28") (pintype "passive"))
      (node (ref "J1") (pin "1") (pinfunction "1_1") (pintype "passive"))
      (node (ref "R44") (pin "2") (pinfunction "2_2") (pintype "passive"))
      (node (ref "R45") (pin "2") (pinfunction "2_2") (pintype "passive"))
      (node (ref "R54") (pin "2") (pinfunction "2_2") (pintype "passive"))
      (node (ref "TP31") (pin "1") (pinfunction "1_1") (pintype "passive"))
      (node (ref "TP33") (pin "1") (pinfunction "1_1") (pintype "passive"))
      (node (ref "TP35") (pin "1") (pinfunction "1_1") (pintype "passive"))
      (node (ref "TP37") (pin "1") (pinfunction "1_1") (pintype "passive"))
      (node (ref "U1") (pin "20") (pinfunction "VCC_20") (pintype "passive"))
      (node (ref "U1") (pin "4") (pinfunction "VCCIO_4") (pintype "passive"))
    )
    (net (code "3") (name "/CPU_CS") (class "Default")
      (node (ref "R12") (pin "2") (pinfunction "2_2") (pintype "passive"))
      (node (ref "R41") (pin "2") (pinfunction "2_2") (pintype "passive"))
    )
    (net (code "4") (name "/CPU_D0") (class "Default")
      (node (ref "R17") (pin "1") (pinfunction "1_1") (pintype "passive"))
      (node (ref "R4") (pin "1") (pinfunction "1_1") (pintype "passive"))
    )
    (net (code "5") (name "/CPU_D1") (class "Default")
      (node (ref "R19") (pin "1") (pinfunction "1_1") (pintype "passive"))
      (node (ref "R6") (pin "1") (pinfunction "1_1") (pintype "passive"))
    )
    (net (code "6") (name "/CPU_D2") (class "Default")
      (node (ref "R21") (pin "1") (pinfunction "1_1") (pintype "passive"))
      (node (ref "R7") (pin "1") (pinfunction "1_1") (pintype "passive"))
    )
    (net (code "7") (name "/CPU_D3") (class "Default")
      (node (ref "R23") (pin "1") (pinfunction "1_1") (pintype "passive"))
      (node (ref "R9") (pin "1") (pinfunction "1_1") (pintype "passive"))
    )
    (net (code "8") (name "/CPU_D4") (class "Default")
      (node (ref "R11") (pin "1") (pinfunction "1_1") (pintype "passive"))
      (node (ref "R25") (pin "1") (pinfunction "1_1") (pintype "passive"))
    )
    (net (code "9") (name "/CPU_D5") (class "Default")
      (node (ref "R13") (pin "1") (pinfunction "1_1") (pintype "passive"))
      (node (ref "R27") (pin "1") (pinfunction "1_1") (pintype "passive"))
    )
    (net (code "10") (name "/CPU_D6") (class "Default")
      (node (ref "R15") (pin "1") (pinfunction "1_1") (pintype "passive"))
      (node (ref "R29") (pin "1") (pinfunction "1_1") (pintype "passive"))
    )
    (net (code "11") (name "/CPU_D7") (class "Default")
      (node (ref "R16") (pin "1") (pinfunction "1_1") (pintype "passive"))
      (node (ref "R31") (pin "1") (pinfunction "1_1") (pintype "passive"))
    )
    (net (code "12") (name "/CPU_Reset") (class "Default")
      (node (ref "R14") (pin "2") (pinfunction "2_2") (pintype "passive"))
      (node (ref "R20") (pin "2") (pinfunction "2_2") (pintype "passive"))
    )
    (net (code "13") (name "/CPU_RnW") (class "Default")
      (node (ref "R10") (pin "2") (pinfunction "2_2") (pintype "passive"))
      (node (ref "R42") (pin "2") (pinfunction "2_2") (pintype "passive"))
    )
    (net (code "14") (name "/CPU_nInt") (class "Default")
      (node (ref "R43") (pin "2") (pinfunction "2_2") (pintype "passive"))
      (node (ref "R8") (pin "2") (pinfunction "2_2") (pintype "passive"))
    )
    (net (code "15") (name "/RXD") (class "Default")
      (node (ref "R36") (pin "1") (pinfunction "1_1") (pintype "passive"))
      (node (ref "R47") (pin "1") (pinfunction "1_1") (pintype "passive"))
    )
    (net (code "16") (name "/TXD") (class "Default")
      (node (ref "R34") (pin "1") (pinfunction "1_1") (pintype "passive"))
      (node (ref "R49") (pin "1") (pinfunction "1_1") (pintype "passive"))
    )
    (net (code "17") (name "/UPDI") (class "Default")
      (node (ref "R1") (pin "1") (pinfunction "1_1") (pintype "passive"))
      (node (ref "R18") (pin "2") (pinfunction "2_2") (pintype "passive"))
    )
    (net (code "18") (name "/USBDM") (class "Default")
      (node (ref "R51") (pin "2") (pinfunction "2_2") (pintype "passive"))
      (node (ref "R57") (pin "1") (pinfunction "1_1") (pintype "passive"))
    )
    (net (code "19") (name "/USBDP") (class "Default")
      (node (ref "R53") (pin "2") (pinfunction "2_2") (pintype "passive"))
      (node (ref "R59") (pin "1") (pinfunction "1_1") (pintype "passive"))
    )
    (net (code "20") (name "GND") (class "Default")
      (node (ref "C1") (pin "2") (pinfunction "2_2") (pintype "passive"))
      (node (ref "C2") (pin "2") (pinfunction "2_2") (pintype "passive"))
      (node (ref "C3") (pin "2") (pinfunction "2_2") (pintype "passive"))
      (node (ref "C4") (pin "2") (pinfunction "2_2") (pintype "passive"))
      (node (ref "C5") (pin "2") (pinfunction "2_2") (pintype "passive"))
      (node (ref "C6") (pin "2") (pinfunction "2_2") (pintype "passive"))
      (node (ref "H1") (pin "6") (pinfunction "GND_6") (pintype "passive"))
      (node (ref "H2") (pin "13") (pinfunction "13_13") (pintype "passive"))
      (node (ref "H2") (pin "15") (pinfunction "15_15") (pintype "passive"))
      (node (ref "IC1") (pin "19") (pinfunction "GND_1_19") (pintype "passive"))
      (node (ref "IC1") (pin "29") (pinfunction "GND_2_29") (pintype "passive"))
      (node (ref "J1") (pin "4") (pinfunction "4_4") (pintype "passive"))
      (node (ref "J1") (pin "5") (pinfunction "5_5") (pintype "passive"))
      (node (ref "J1") (pin "6") (pinfunction "Shield_6") (pintype "passive"))
      (node (ref "J1") (pin "7") (pinfunction "Shield_7") (pintype "passive"))
      (node (ref "J1") (pin "8") (pinfunction "Shield_8") (pintype "passive"))
      (node (ref "J1") (pin "9") (pinfunction "Shield5_9") (pintype "passive"))
      (node (ref "R67") (pin "1") (pinfunction "1_1") (pintype "passive"))
      (node (ref "TP32") (pin "1") (pinfunction "1_1") (pintype "passive"))
      (node (ref "TP34") (pin "1") (pinfunction "1_1") (pintype "passive"))
      (node (ref "TP36") (pin "1") (pinfunction "1_1") (pintype "passive"))
      (node (ref "TP38") (pin "1") (pinfunction "1_1") (pintype "passive"))
      (node (ref "U1") (pin "18") (pinfunction "GND_2_18") (pintype "passive"))
      (node (ref "U1") (pin "21") (pinfunction "GND_3_21") (pintype "passive"))
      (node (ref "U1") (pin "25") (pinfunction "AGND_25") (pintype "passive"))
      (node (ref "U1") (pin "26") (pinfunction "TEST_26") (pintype "passive"))
      (node (ref "U1") (pin "7") (pinfunction "GND_1_7") (pintype "passive"))
    )
    (net (code "21") (name "Net-(H1-NC-Pad3)") (class "Default")
      (node (ref "H1") (pin "3") (pinfunction "NC_3") (pintype "passive"))
      (node (ref "R2") (pin "2") (pinfunction "2_2") (pintype "passive"))
    )
    (net (code "22") (name "Net-(H1-NC-Pad4)") (class "Default")
      (node (ref "H1") (pin "4") (pinfunction "NC_4") (pintype "passive"))
      (node (ref "R3") (pin "1") (pinfunction "1_1") (pintype "passive"))
    )
    (net (code "23") (name "Net-(H1-NC-Pad5)") (class "Default")
      (node (ref "H1") (pin "5") (pinfunction "NC_5") (pintype "passive"))
      (node (ref "R5") (pin "2") (pinfunction "2_2") (pintype "passive"))
    )
    (net (code "24") (name "Net-(H1-UDPI)") (class "Default")
      (node (ref "H1") (pin "1") (pinfunction "UDPI_1") (pintype "passive"))
      (node (ref "R1") (pin "2") (pinfunction "2_2") (pintype "passive"))
    )
    (net (code "25") (name "Net-(H2-Pad2)") (class "Default")
      (node (ref "H2") (pin "2") (pinfunction "2_2") (pintype "passive"))
      (node (ref "R4") (pin "2") (pinfunction "2_2") (pintype "passive"))
    )
    (net (code "26") (name "Net-(H2-Pad4)") (class "Default")
      (node (ref "H2") (pin "4") (pinfunction "4_4") (pintype "passive"))
      (node (ref "R6") (pin "2") (pinfunction "2_2") (pintype "passive"))
    )
    (net (code "27") (name "Net-(H2-Pad5)") (class "Default")
      (node (ref "H2") (pin "5") (pinfunction "5_5") (pintype "passive"))
      (node (ref "R8") (pin "1") (pinfunction "1_1") (pintype "passive"))
    )
    (net (code "28") (name "Net-(H2-Pad6)") (class "Default")
      (node (ref "H2") (pin "6") (pinfunction "6_6") (pintype "passive"))
      (node (ref "R7") (pin "2") (pinfunction "2_2") (pintype "passive"))
    )
    (net (code "29") (name "Net-(H2-Pad7)") (class "Default")
      (node (ref "H2") (pin "7") (pinfunction "7_7") (pintype "passive"))
      (node (ref "R10") (pin "1") (pinfunction "1_1") (pintype "passive"))
    )
    (net (code "30") (name "Net-(H2-Pad8)") (class "Default")
      (node (ref "H2") (pin "8") (pinfunction "8_8") (pintype "passive"))
      (node (ref "R9") (pin "2") (pinfunction "2_2") (pintype "passive"))
    )
    (net (code "31") (name "Net-(H2-Pad9)") (class "Default")
      (node (ref "H2") (pin "9") (pinfunction "9_9") (pintype "passive"))
      (node (ref "R12") (pin "1") (pinfunction "1_1") (pintype "passive"))
    )
    (net (code "32") (name "Net-(H2-Pad10)") (class "Default")
      (node (ref "H2") (pin "10") (pinfunction "10_10") (pintype "passive"))
      (node (ref "R11") (pin "2") (pinfunction "2_2") (pintype "passive"))
    )
    (net (code "33") (name "Net-(H2-Pad11)") (class "Default")
      (node (ref "H2") (pin "11") (pinfunction "11_11") (pintype "passive"))
      (node (ref "R14") (pin "1") (pinfunction "1_1") (pintype "passive"))
    )
    (net (code "34") (name "Net-(H2-Pad12)") (class "Default")
      (node (ref "H2") (pin "12") (pinfunction "12_12") (pintype "passive"))
      (node (ref "R13") (pin "2") (pinfunction "2_2") (pintype "passive"))
    )
    (net (code "35") (name "Net-(H2-Pad14)") (class "Default")
      (node (ref "H2") (pin "14") (pinfunction "14_14") (pintype "passive"))
      (node (ref "R15") (pin "2") (pinfunction "2_2") (pintype "passive"))
    )
    (net (code "36") (name "Net-(H2-Pad16)") (class "Default")
      (node (ref "H2") (pin "16") (pinfunction "16_16") (pintype "passive"))
      (node (ref "R16") (pin "2") (pinfunction "2_2") (pintype "passive"))
    )
    (net (code "37") (name "Net-(IC1-PA0)") (class "Default")
      (node (ref "IC1") (pin "30") (pinfunction "PA0_30") (pintype "passive"))
      (node (ref "R17") (pin "2") (pinfunction "2_2") (pintype "passive"))
    )
    (net (code "38") (name "Net-(IC1-PA1)") (class "Default")
      (node (ref "IC1") (pin "31") (pinfunction "PA1_31") (pintype "passive"))
      (node (ref "R19") (pin "2") (pinfunction "2_2") (pintype "passive"))
    )
    (net (code "39") (name "Net-(IC1-PA2)") (class "Default")
      (node (ref "IC1") (pin "32") (pinfunction "PA2_32") (pintype "passive"))
      (node (ref "R21") (pin "2") (pinfunction "2_2") (pintype "passive"))
    )
    (net (code "40") (name "Net-(IC1-PA3)") (class "Default")
      (node (ref "IC1") (pin "1") (pinfunction "PA3_1") (pintype "passive"))
      (node (ref "R23") (pin "2") (pinfunction "2_2") (pintype "passive"))
    )
    (net (code "41") (name "Net-(IC1-PA4)") (class "Default")
      (node (ref "IC1") (pin "2") (pinfunction "PA4_2") (pintype "passive"))
      (node (ref "R25") (pin "2") (pinfunction "2_2") (pintype "passive"))
    )
    (net (code "42") (name "Net-(IC1-PA5)") (class "Default")
      (node (ref "IC1") (pin "3") (pinfunction "PA5_3") (pintype "passive"))
      (node (ref "R27") (pin "2") (pinfunction "2_2") (pintype "passive"))
    )
    (net (code "43") (name "Net-(IC1-PA6)") (class "Default")
      (node (ref "IC1") (pin "4") (pinfunction "PA6_4") (pintype "passive"))
      (node (ref "R29") (pin "2") (pinfunction "2_2") (pintype "passive"))
    )
    (net (code "44") (name "Net-(IC1-PA7)") (class "Default")
      (node (ref "IC1") (pin "5") (pinfunction "PA7_5") (pintype "passive"))
      (node (ref "R31") (pin "2") (pinfunction "2_2") (pintype "passive"))
    )
    (net (code "45") (name "Net-(IC1-PC0)") (class "Default")
      (node (ref "IC1") (pin "6") (pinfunction "PC0_6") (pintype "passive"))
      (node (ref "R34") (pin "2") (pinfunction "2_2") (pintype "passive"))
    )
    (net (code "46") (name "Net-(IC1-PC1)") (class "Default")
      (node (ref "IC1") (pin "7") (pinfunction "PC1_7") (pintype "passive"))
      (node (ref "R36") (pin "2") (pinfunction "2_2") (pintype "passive"))
    )
    (net (code "47") (name "Net-(IC1-PC2)") (class "Default")
      (node (ref "IC1") (pin "8") (pinfunction "PC2_8") (pintype "passive"))
      (node (ref "R38") (pin "2") (pinfunction "2_2") (pintype "passive"))
    )
    (net (code "48") (name "Net-(IC1-PC3)") (class "Default")
      (node (ref "IC1") (pin "9") (pinfunction "PC3_9") (pintype "passive"))
      (node (ref "R40") (pin "2") (pinfunction "2_2") (pintype "passive"))
    )
    (net (code "49") (name "Net-(IC1-PD3)") (class "Default")
      (node (ref "IC1") (pin "13") (pinfunction "PD3_13") (pintype "passive"))
      (node (ref "R41") (pin "1") (pinfunction "1_1") (pintype "passive"))
    )
    (net (code "50") (name "Net-(IC1-PD4)") (class "Default")
      (node (ref "IC1") (pin "14") (pinfunction "PD4_14") (pintype "passive"))
      (node (ref "R39") (pin "1") (pinfunction "1_1") (pintype "passive"))
    )
    (net (code "51") (name "Net-(IC1-PD5)") (class "Default")
      (node (ref "IC1") (pin "15") (pinfunction "PD5_15") (pintype "passive"))
      (node (ref "R37") (pin "1") (pinfunction "1_1") (pintype "passive"))
    )
    (net (code "52") (name "Net-(IC1-PD6)") (class "Default")
      (node (ref "IC1") (pin "16") (pinfunction "PD6_16") (pintype "passive"))
      (node (ref "R35") (pin "1") (pinfunction "1_1") (pintype "passive"))
    )
    (net (code "53") (name "Net-(IC1-PD7)") (class "Default")
      (node (ref "IC1") (pin "17") (pinfunction "PD7_17") (pintype "passive"))
      (node (ref "R33") (pin "1") (pinfunction "1_1") (pintype "passive"))
    )
    (net (code "54") (name "Net-(IC1-PD~{1})") (class "Default")
      (node (ref "IC1") (pin "11") (pinfunction "PD~{1}_11") (pintype "passive"))
      (node (ref "R43") (pin "1") (pinfunction "1_1") (pintype "passive"))
    )
    (net (code "55") (name "Net-(IC1-PD~{2})") (class "Default")
      (node (ref "IC1") (pin "12") (pinfunction "PD~{2}_12") (pintype "passive"))
      (node (ref "R42") (pin "1") (pinfunction "1_1") (pintype "passive"))
    )
    (net (code "56") (name "Net-(IC1-PF0)") (class "Default")
      (node (ref "IC1") (pin "20") (pinfunction "PF0_20") (pintype "passive"))
      (node (ref "R32") (pin "1") (pinfunction "1_1") (pintype "passive"))
    )
    (net (code "57") (name "Net-(IC1-PF1)") (class "Default")
      (node (ref "IC1") (pin "21") (pinfunction "PF1_21") (pintype "passive"))
      (node (ref "R30") (pin "1") (pinfunction "1_1") (pintype "passive"))
    )
    (net (code "58") (name "Net-(IC1-PF2)") (class "Default")
      (node (ref "IC1") (pin "22") (pinfunction "PF2_22") (pintype "passive"))
      (node (ref "R28") (pin "1") (pinfunction "1_1") (pintype "passive"))
    )
    (net (code "59") (name "Net-(IC1-PF3)") (class "Default")
      (node (ref "IC1") (pin "23") (pinfunction "PF3_23") (pintype "passive"))
      (node (ref "R26") (pin "1") (pinfunction "1_1") (pintype "passive"))
    )
    (net (code "60") (name "Net-(IC1-PF4)") (class "Default")
      (node (ref "IC1") (pin "24") (pinfunction "PF4_24") (pintype "passive"))
      (node (ref "R24") (pin "1") (pinfunction "1_1") (pintype "passive"))
    )
    (net (code "61") (name "Net-(IC1-PF5)") (class "Default")
      (node (ref "IC1") (pin "25") (pinfunction "PF5_25") (pintype "passive"))
      (node (ref "R22") (pin "1") (pinfunction "1_1") (pintype "passive"))
    )
    (net (code "62") (name "Net-(IC1-PF6_(~{RESET)})") (class "Default")
      (node (ref "IC1") (pin "26") (pinfunction "PF6_(~{RESET)}_26") (pintype "passive"))
      (node (ref "R20") (pin "1") (pinfunction "1_1") (pintype "passive"))
    )
    (net (code "63") (name "Net-(IC1-PF7_(UPDI))") (class "Default")
      (node (ref "IC1") (pin "27") (pinfunction "PF7_(UPDI)_27") (pintype "passive"))
      (node (ref "R18") (pin "1") (pinfunction "1_1") (pintype "passive"))
    )
    (net (code "64") (name "Net-(J1-Pad2)") (class "Default")
      (node (ref "J1") (pin "2") (pinfunction "2_2") (pintype "passive"))
      (node (ref "R51") (pin "1") (pinfunction "1_1") (pintype "passive"))
    )
    (net (code "65") (name "Net-(J1-Pad3)") (class "Default")
      (node (ref "J1") (pin "3") (pinfunction "3_3") (pintype "passive"))
      (node (ref "R53") (pin "1") (pinfunction "1_1") (pintype "passive"))
    )
    (net (code "66") (name "Net-(LED1-A)") (class "Default")
      (node (ref "LED1") (pin "2") (pinfunction "A_2") (pintype "passive"))
      (node (ref "R44") (pin "1") (pinfunction "1_1") (pintype "passive"))
    )
    (net (code "67") (name "Net-(LED1-K)") (class "Default")
      (node (ref "LED1") (pin "1") (pinfunction "K_1") (pintype "passive"))
      (node (ref "U1") (pin "23") (pinfunction "CBUS0_23") (pintype "passive"))
    )
    (net (code "68") (name "Net-(LED2-A)") (class "Default")
      (node (ref "LED2") (pin "2") (pinfunction "A_2") (pintype "passive"))
      (node (ref "R45") (pin "1") (pinfunction "1_1") (pintype "passive"))
    )
    (net (code "69") (name "Net-(LED2-K)") (class "Default")
      (node (ref "LED2") (pin "1") (pinfunction "K_1") (pintype "passive"))
      (node (ref "U1") (pin "22") (pinfunction "CBUS1_22") (pintype "passive"))
    )
    (net (code "70") (name "Net-(R2-Pad1)") (class "Default")
      (node (ref "R2") (pin "1") (pinfunction "1_1") (pintype "passive"))
      (node (ref "TP1") (pin "1") (pinfunction "1_1") (pintype "passive"))
    )
    (net (code "71") (name "Net-(R3-Pad2)") (class "Default")
      (node (ref "R3") (pin "2") (pinfunction "2_2") (pintype "passive"))
      (node (ref "TP2") (pin "1") (pinfunction "1_1") (pintype "passive"))
    )
    (net (code "72") (name "Net-(R5-Pad1)") (class "Default")
      (node (ref "R5") (pin "1") (pinfunction "1_1") (pintype "passive"))
      (node (ref "TP3") (pin "1") (pinfunction "1_1") (pintype "passive"))
    )
    (net (code "73") (name "Net-(R22-Pad2)") (class "Default")
      (node (ref "R22") (pin "2") (pinfunction "2_2") (pintype "passive"))
      (node (ref "TP5") (pin "1") (pinfunction "1_1") (pintype "passive"))
    )
    (net (code "74") (name "Net-(R24-Pad2)") (class "Default")
      (node (ref "R24") (pin "2") (pinfunction "2_2") (pintype "passive"))
      (node (ref "TP6") (pin "1") (pinfunction "1_1") (pintype "passive"))
    )
    (net (code "75") (name "Net-(R26-Pad2)") (class "Default")
      (node (ref "R26") (pin "2") (pinfunction "2_2") (pintype "passive"))
      (node (ref "TP7") (pin "1") (pinfunction "1_1") (pintype "passive"))
    )
    (net (code "76") (name "Net-(R28-Pad2)") (class "Default")
      (node (ref "R28") (pin "2") (pinfunction "2_2") (pintype "passive"))
      (node (ref "TP8") (pin "1") (pinfunction "1_1") (pintype "passive"))
    )
    (net (code "77") (name "Net-(R30-Pad2)") (class "Default")
      (node (ref "R30") (pin "2") (pinfunction "2_2") (pintype "passive"))
      (node (ref "TP9") (pin "1") (pinfunction "1_1") (pintype "passive"))
    )
    (net (code "78") (name "Net-(R32-Pad2)") (class "Default")
      (node (ref "R32") (pin "2") (pinfunction "2_2") (pintype "passive"))
      (node (ref "TP10") (pin "1") (pinfunction "1_1") (pintype "passive"))
    )
    (net (code "79") (name "Net-(R33-Pad2)") (class "Default")
      (node (ref "R33") (pin "2") (pinfunction "2_2") (pintype "passive"))
      (node (ref "TP11") (pin "1") (pinfunction "1_1") (pintype "passive"))
    )
    (net (code "80") (name "Net-(R35-Pad2)") (class "Default")
      (node (ref "R35") (pin "2") (pinfunction "2_2") (pintype "passive"))
      (node (ref "TP12") (pin "1") (pinfunction "1_1") (pintype "passive"))
    )
    (net (code "81") (name "Net-(R37-Pad2)") (class "Default")
      (node (ref "R37") (pin "2") (pinfunction "2_2") (pintype "passive"))
      (node (ref "TP13") (pin "1") (pinfunction "1_1") (pintype "passive"))
    )
    (net (code "82") (name "Net-(R38-Pad1)") (class "Default")
      (node (ref "R38") (pin "1") (pinfunction "1_1") (pintype "passive"))
      (node (ref "TP14") (pin "1") (pinfunction "1_1") (pintype "passive"))
    )
    (net (code "83") (name "Net-(R39-Pad2)") (class "Default")
      (node (ref "R39") (pin "2") (pinfunction "2_2") (pintype "passive"))
      (node (ref "TP15") (pin "1") (pinfunction "1_1") (pintype "passive"))
    )
    (net (code "84") (name "Net-(R40-Pad1)") (class "Default")
      (node (ref "R40") (pin "1") (pinfunction "1_1") (pintype "passive"))
      (node (ref "TP16") (pin "1") (pinfunction "1_1") (pintype "passive"))
    )
    (net (code "85") (name "Net-(R46-Pad2)") (class "Default")
      (node (ref "R46") (pin "2") (pinfunction "2_2") (pintype "passive"))
      (node (ref "TP17") (pin "1") (pinfunction "1_1") (pintype "passive"))
    )
    (net (code "86") (name "Net-(R48-Pad2)") (class "Default")
      (node (ref "R48") (pin "2") (pinfunction "2_2") (pintype "passive"))
      (node (ref "TP18") (pin "1") (pinfunction "1_1") (pintype "passive"))
    )
    (net (code "87") (name "Net-(R50-Pad2)") (class "Default")
      (node (ref "R50") (pin "2") (pinfunction "2_2") (pintype "passive"))
      (node (ref "TP19") (pin "1") (pinfunction "1_1") (pintype "passive"))
    )
    (net (code "88") (name "Net-(R52-Pad2)") (class "Default")
      (node (ref "R52") (pin "2") (pinfunction "2_2") (pintype "passive"))
      (node (ref "TP20") (pin "1") (pinfunction "1_1") (pintype "passive"))
    )
    (net (code "89") (name "Net-(R55-Pad2)") (class "Default")
      (node (ref "R55") (pin "2") (pinfunction "2_2") (pintype "passive"))
      (node (ref "TP21") (pin "1") (pinfunction "1_1") (pintype "passive"))
    )
    (net (code "90") (name "Net-(R56-Pad2)") (class "Default")
      (node (ref "R56") (pin "2") (pinfunction "2_2") (pintype "passive"))
      (node (ref "TP22") (pin "1") (pinfunction "1_1") (pintype "passive"))
    )
    (net (code "91") (name "Net-(R58-Pad2)") (class "Default")
      (node (ref "R58") (pin "2") (pinfunction "2_2") (pintype "passive"))
      (node (ref "TP23") (pin "1") (pinfunction "1_1") (pintype "passive"))
    )
    (net (code "92") (name "Net-(R60-Pad2)") (class "Default")
      (node (ref "R60") (pin "2") (pinfunction "2_2") (pintype "passive"))
      (node (ref "TP24") (pin "1") (pinfunction "1_1") (pintype "passive"))
    )
    (net (code "93") (name "Net-(R61-Pad2)") (class "Default")
      (node (ref "R61") (pin "2") (pinfunction "2_2") (pintype "passive"))
      (node (ref "TP25") (pin "1") (pinfunction "1_1") (pintype "passive"))
    )
    (net (code "94") (name "Net-(R62-Pad2)") (class "Default")
      (node (ref "R62") (pin "2") (pinfunction "2_2") (pintype "passive"))
      (node (ref "TP26") (pin "1") (pinfunction "1_1") (pintype "passive"))
    )
    (net (code "95") (name "Net-(R63-Pad2)") (class "Default")
      (node (ref "R63") (pin "2") (pinfunction "2_2") (pintype "passive"))
      (node (ref "TP27") (pin "1") (pinfunction "1_1") (pintype "passive"))
    )
    (net (code "96") (name "Net-(R64-Pad2)") (class "Default")
      (node (ref "R64") (pin "2") (pinfunction "2_2") (pintype "passive"))
      (node (ref "TP28") (pin "1") (pinfunction "1_1") (pintype "passive"))
    )
    (net (code "97") (name "Net-(R65-Pad2)") (class "Default")
      (node (ref "R65") (pin "2") (pinfunction "2_2") (pintype "passive"))
      (node (ref "TP29") (pin "1") (pinfunction "1_1") (pintype "passive"))
    )
    (net (code "98") (name "Net-(R66-Pad2)") (class "Default")
      (node (ref "R66") (pin "2") (pinfunction "2_2") (pintype "passive"))
      (node (ref "TP30") (pin "1") (pinfunction "1_1") (pintype "passive"))
    )
    (net (code "99") (name "Net-(U1-3V3OUT)") (class "Default")
      (node (ref "R46") (pin "1") (pinfunction "1_1") (pintype "passive"))
      (node (ref "U1") (pin "17") (pinfunction "3V3OUT_17") (pintype "passive"))
    )
    (net (code "100") (name "Net-(U1-CBUS2)") (class "Default")
      (node (ref "R62") (pin "1") (pinfunction "1_1") (pintype "passive"))
      (node (ref "U1") (pin "13") (pinfunction "CBUS2_13") (pintype "passive"))
    )
    (net (code "101") (name "Net-(U1-CBUS3)") (class "Default")
      (node (ref "R63") (pin "1") (pinfunction "1_1") (pintype "passive"))
      (node (ref "U1") (pin "14") (pinfunction "CBUS3_14") (pintype "passive"))
    )
    (net (code "102") (name "Net-(U1-CBUS4)") (class "Default")
      (node (ref "R61") (pin "1") (pinfunction "1_1") (pintype "passive"))
      (node (ref "U1") (pin "12") (pinfunction "CBUS4_12") (pintype "passive"))
    )
    (net (code "103") (name "Net-(U1-CTS#)") (class "Default")
      (node (ref "R60") (pin "1") (pinfunction "1_1") (pintype "passive"))
      (node (ref "U1") (pin "11") (pinfunction "CTS#_11") (pintype "passive"))
    )
    (net (code "104") (name "Net-(U1-DCD#)") (class "Default")
      (node (ref "R58") (pin "1") (pinfunction "1_1") (pintype "passive"))
      (node (ref "U1") (pin "10") (pinfunction "DCD#_10") (pintype "passive"))
    )
    (net (code "105") (name "Net-(U1-DSR#)") (class "Default")
      (node (ref "R56") (pin "1") (pinfunction "1_1") (pintype "passive"))
      (node (ref "U1") (pin "9") (pinfunction "DSR#_9") (pintype "passive"))
    )
    (net (code "106") (name "Net-(U1-DTR#)") (class "Default")
      (node (ref "R48") (pin "1") (pinfunction "1_1") (pintype "passive"))
      (node (ref "U1") (pin "2") (pinfunction "DTR#_2") (pintype "passive"))
    )
    (net (code "107") (name "Net-(U1-NC_1)") (class "Default")
      (node (ref "R55") (pin "1") (pinfunction "1_1") (pintype "passive"))
      (node (ref "U1") (pin "8") (pinfunction "NC_1_8") (pintype "passive"))
    )
    (net (code "108") (name "Net-(U1-NC_2)") (class "Default")
      (node (ref "R64") (pin "1") (pinfunction "1_1") (pintype "passive"))
      (node (ref "U1") (pin "24") (pinfunction "NC_2_24") (pintype "passive"))
    )
    (net (code "109") (name "Net-(U1-OSCI)") (class "Default")
      (node (ref "R65") (pin "1") (pinfunction "1_1") (pintype "passive"))
      (node (ref "U1") (pin "27") (pinfunction "OSCI_27") (pintype "passive"))
    )
    (net (code "110") (name "Net-(U1-OSCO)") (class "Default")
      (node (ref "R66") (pin "1") (pinfunction "1_1") (pintype "passive"))
      (node (ref "U1") (pin "28") (pinfunction "OSCO_28") (pintype "passive"))
    )
    (net (code "111") (name "Net-(U1-RESET#)") (class "Default")
      (node (ref "R54") (pin "1") (pinfunction "1_1") (pintype "passive"))
      (node (ref "R67") (pin "2") (pinfunction "2_2") (pintype "passive"))
      (node (ref "U1") (pin "19") (pinfunction "RESET#_19") (pintype "passive"))
    )
    (net (code "112") (name "Net-(U1-RI#)") (class "Default")
      (node (ref "R52") (pin "1") (pinfunction "1_1") (pintype "passive"))
      (node (ref "U1") (pin "6") (pinfunction "RI#_6") (pintype "passive"))
    )
    (net (code "113") (name "Net-(U1-RTS#)") (class "Default")
      (node (ref "R50") (pin "1") (pinfunction "1_1") (pintype "passive"))
      (node (ref "U1") (pin "3") (pinfunction "RTS#_3") (pintype "passive"))
    )
    (net (code "114") (name "Net-(U1-RXD)") (class "Default")
      (node (ref "R49") (pin "2") (pinfunction "2_2") (pintype "passive"))
      (node (ref "U1") (pin "5") (pinfunction "RXD_5") (pintype "passive"))
    )
    (net (code "115") (name "Net-(U1-TXD)") (class "Default")
      (node (ref "R47") (pin "2") (pinfunction "2_2") (pintype "passive"))
      (node (ref "U1") (pin "1") (pinfunction "TXD_1") (pintype "passive"))
    )
    (net (code "116") (name "Net-(U1-USBDM)") (class "Default")
      (node (ref "R57") (pin "2") (pinfunction "2_2") (pintype "passive"))
      (node (ref "U1") (pin "16") (pinfunction "USBDM_16") (pintype "passive"))
    )
    (net (code "117") (name "Net-(U1-USBDP)") (class "Default")
      (node (ref "R59") (pin "2") (pinfunction "2_2") (pintype "passive"))
      (node (ref "U1") (pin "15") (pinfunction "USBDP_15") (pintype "passive"))
    )
  )
)
